# RCShield-arm-v0.net
KiCad netlist of a schematic drawn in EAGLE
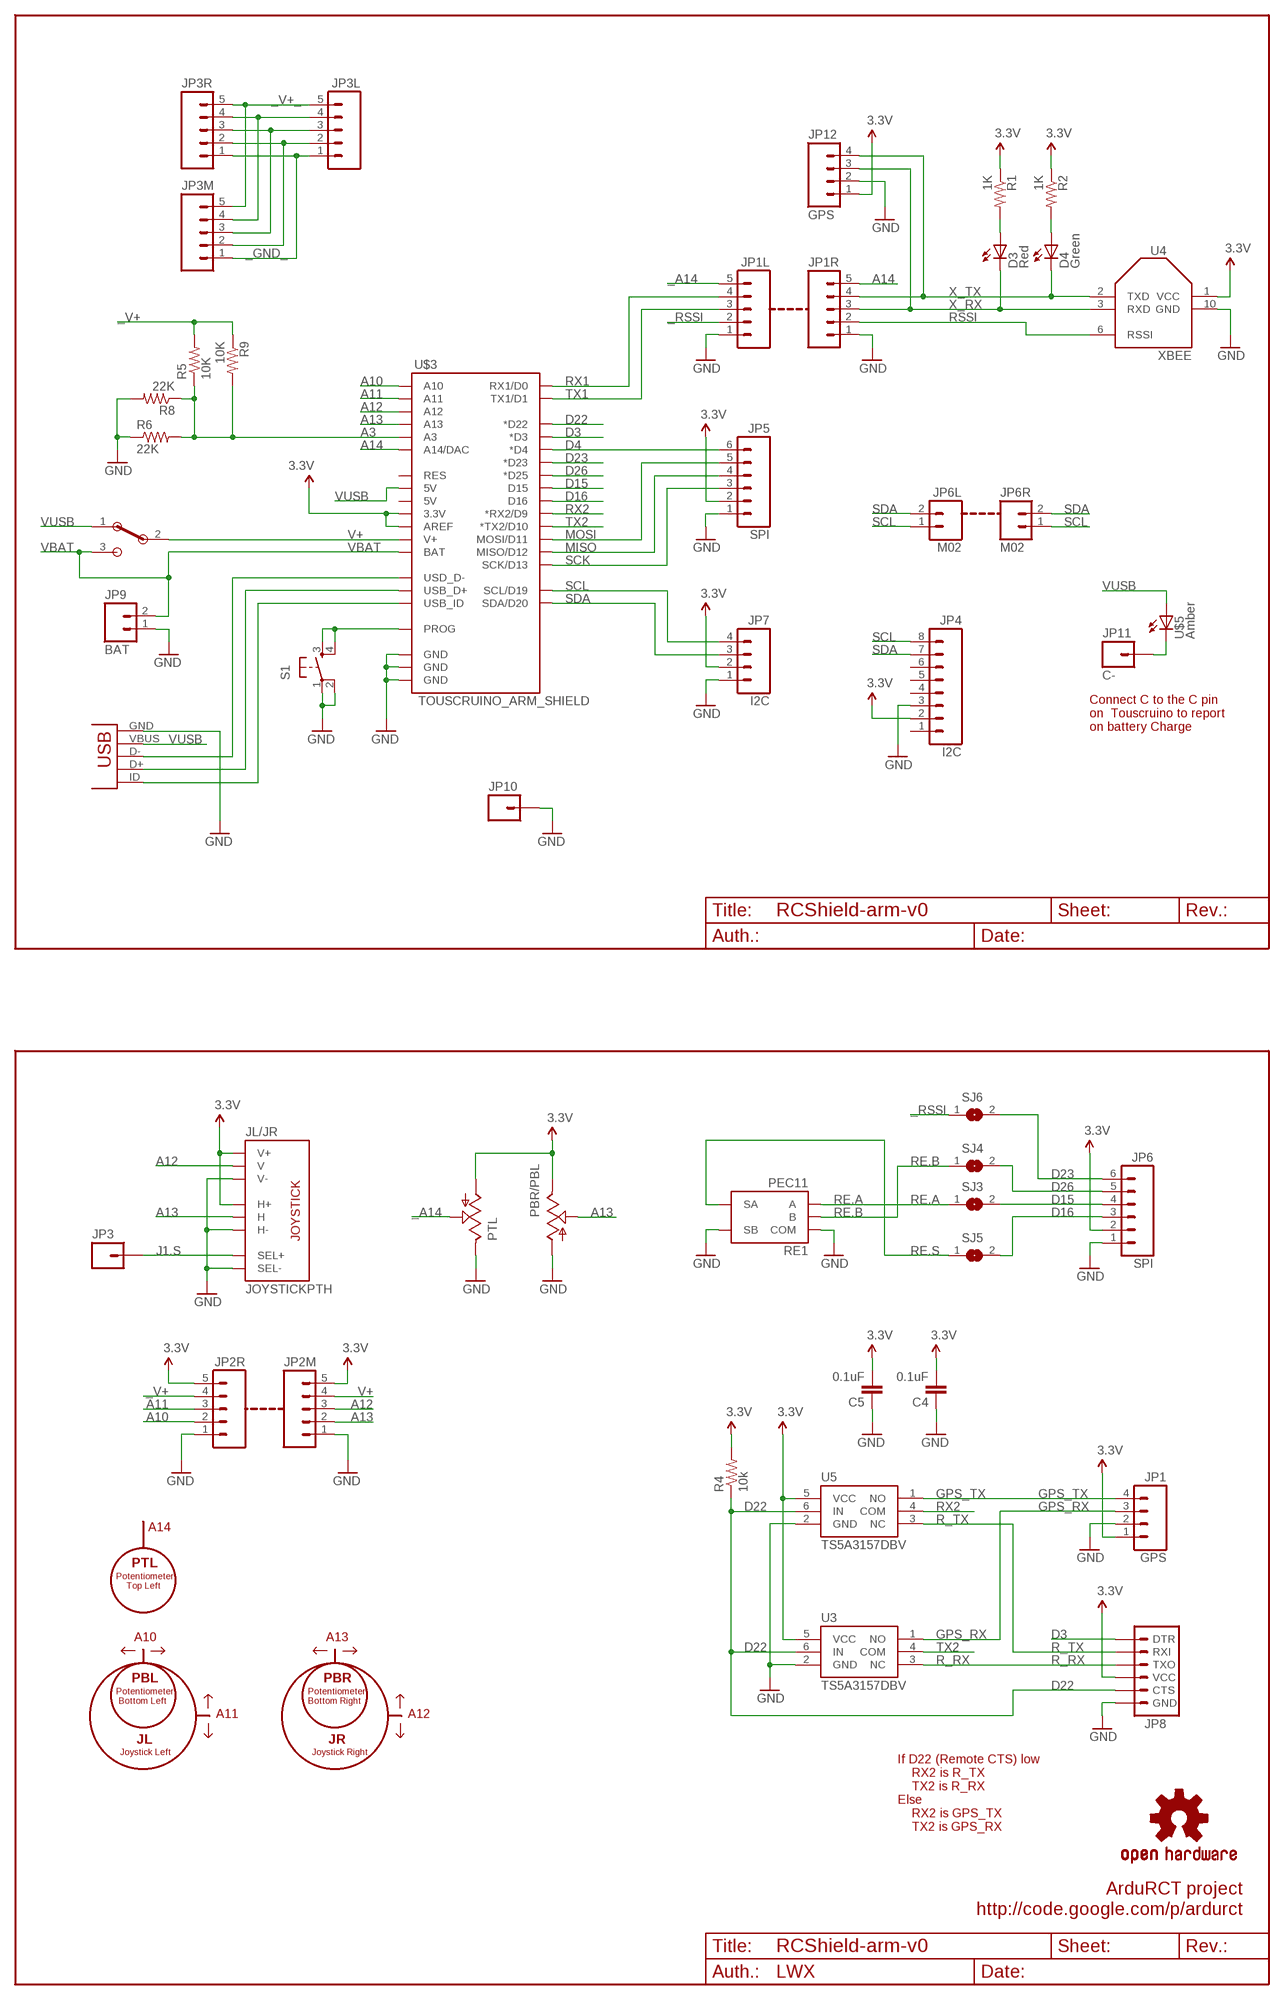
[diagram p0: schematic, sheet 1]

(export (version "E")
  (design (tool "Eeschema 10.0.6"))
  (components
    (comp (ref "C4")
      (value "0.1uF")
      (footprint "eagle-import:0805")
      (libsource (lib "eagle-import") (part "CAP0805"))
    )
    (comp (ref "C5")
      (value "0.1uF")
      (footprint "eagle-import:0805")
      (libsource (lib "eagle-import") (part "CAP0805"))
    )
    (comp (ref "D3")
      (value "Red")
      (footprint "eagle-import:LED")
      (libsource (lib "eagle-import") (part "LED"))
    )
    (comp (ref "D4")
      (value "Green")
      (footprint "eagle-import:LED")
      (libsource (lib "eagle-import") (part "LED"))
    )
    (comp (ref "JL/JR")
      (value "JOYSTICKPTH")
      (footprint "eagle-import:JOYSTICK")
      (libsource (lib "eagle-import") (part "JOYSTICKPTH"))
    )
    (comp (ref "JP1")
      (value "GPS")
      (footprint "eagle-import:1X04")
      (libsource (lib "eagle-import") (part "M04"))
    )
    (comp (ref "JP1L")
      (value "M05")
      (footprint "eagle-import:2+3")
      (libsource (lib "eagle-import") (part "M05"))
    )
    (comp (ref "JP1R")
      (value "M05")
      (footprint "eagle-import:2+3")
      (libsource (lib "eagle-import") (part "M05"))
    )
    (comp (ref "JP2M")
      (value "M05")
      (footprint "eagle-import:2+3")
      (libsource (lib "eagle-import") (part "M05"))
    )
    (comp (ref "JP2R")
      (value "M05")
      (footprint "eagle-import:2+3")
      (libsource (lib "eagle-import") (part "M05"))
    )
    (comp (ref "JP3")
      (value "M01PTH")
      (footprint "eagle-import:1X01")
      (libsource (lib "eagle-import") (part "M01PTH"))
    )
    (comp (ref "JP3L")
      (value "M05")
      (footprint "eagle-import:2+3")
      (libsource (lib "eagle-import") (part "M05"))
    )
    (comp (ref "JP3M")
      (value "M05")
      (footprint "eagle-import:2+3")
      (libsource (lib "eagle-import") (part "M05"))
    )
    (comp (ref "JP3R")
      (value "M05")
      (footprint "eagle-import:2+3")
      (libsource (lib "eagle-import") (part "M05"))
    )
    (comp (ref "JP4")
      (value "I2C")
      (footprint "eagle-import:1X08")
      (libsource (lib "eagle-import") (part "M08"))
    )
    (comp (ref "JP5")
      (value "SPI")
      (footprint "eagle-import:1X06")
      (libsource (lib "eagle-import") (part "M06SIP"))
    )
    (comp (ref "JP6")
      (value "SPI")
      (footprint "eagle-import:1X06")
      (libsource (lib "eagle-import") (part "M06SIP"))
    )
    (comp (ref "JP6L")
      (value "M02")
      (footprint "eagle-import:1X02")
      (libsource (lib "eagle-import") (part "M02"))
    )
    (comp (ref "JP6R")
      (value "M02")
      (footprint "eagle-import:1X02")
      (libsource (lib "eagle-import") (part "M02"))
    )
    (comp (ref "JP7")
      (value "I2C")
      (footprint "eagle-import:1X04")
      (libsource (lib "eagle-import") (part "M04"))
    )
    (comp (ref "JP8")
      (value "ARDUINO_SERIAL_PROGRAM")
      (footprint "eagle-import:1X06_F")
      (libsource (lib "eagle-import") (part "ARDUINO_SERIAL_PROGRAM"))
    )
    (comp (ref "JP9")
      (value "BAT")
      (footprint "eagle-import:1X02")
      (libsource (lib "eagle-import") (part "M02"))
    )
    (comp (ref "JP10")
      (value "M01PTH")
      (footprint "eagle-import:1X01")
      (libsource (lib "eagle-import") (part "M01PTH"))
    )
    (comp (ref "JP11")
      (value "C-")
      (footprint "eagle-import:1X01")
      (libsource (lib "eagle-import") (part "M01PTH"))
    )
    (comp (ref "JP12")
      (value "GPS")
      (footprint "eagle-import:1X04")
      (libsource (lib "eagle-import") (part "M04"))
    )
    (comp (ref "PBR/PBL")
      (value "POT")
      (footprint "eagle-import:ALPS_POT")
      (libsource (lib "eagle-import") (part "POT"))
    )
    (comp (ref "PTL")
      (value "POT")
      (footprint "eagle-import:ALPS_POT")
      (libsource (lib "eagle-import") (part "POT"))
    )
    (comp (ref "R1")
      (value "1K")
      (footprint "eagle-import:0805")
      (libsource (lib "eagle-import") (part "RESISTOR0805-RES"))
    )
    (comp (ref "R2")
      (value "1K")
      (footprint "eagle-import:0805")
      (libsource (lib "eagle-import") (part "RESISTOR0805-RES"))
    )
    (comp (ref "R4")
      (value "10k")
      (footprint "eagle-import:0805")
      (libsource (lib "eagle-import") (part "RESISTOR0805-RES"))
    )
    (comp (ref "R5")
      (value "10K")
      (footprint "eagle-import:0805")
      (libsource (lib "eagle-import") (part "RESISTOR0805-RES"))
    )
    (comp (ref "R6")
      (value "22K")
      (footprint "eagle-import:0805")
      (libsource (lib "eagle-import") (part "RESISTOR0805-RES"))
    )
    (comp (ref "R8")
      (value "22K")
      (footprint "eagle-import:0207_7")
      (libsource (lib "eagle-import") (part "R-US_0207/7"))
    )
    (comp (ref "R9")
      (value "10K")
      (footprint "eagle-import:0207_7")
      (libsource (lib "eagle-import") (part "R-US_0207/7"))
    )
    (comp (ref "RE1")
      (value "PEC11")
      (footprint "eagle-import:PEC11")
      (libsource (lib "eagle-import") (part "PEC11"))
    )
    (comp (ref "S1")
      (value "TAC_SWITCHPTH")
      (footprint "eagle-import:TACTILE-PTH")
      (libsource (lib "eagle-import") (part "TAC_SWITCHPTH"))
    )
    (comp (ref "S4")
      (value "EG1224")
      (footprint "eagle-import:EG1224")
      (libsource (lib "eagle-import") (part "EG1224"))
    )
    (comp (ref "SJ3") (value "SJ") (footprint "eagle-import:SJ") (libsource (lib "eagle-import") (part "SJ")))
    (comp (ref "SJ4") (value "SJ") (footprint "eagle-import:SJ") (libsource (lib "eagle-import") (part "SJ")))
    (comp (ref "SJ5") (value "SJ") (footprint "eagle-import:SJ") (libsource (lib "eagle-import") (part "SJ")))
    (comp (ref "SJ6") (value "SJ") (footprint "eagle-import:SJ") (libsource (lib "eagle-import") (part "SJ")))
    (comp (ref "U$1")
      (value "OSHW-LOGOM")
      (footprint "eagle-import:OSHW-LOGO-M")
      (libsource (lib "eagle-import") (part "OSHW-LOGOM"))
    )
    (comp (ref "U$3")
      (value "TOUSCRUINO_ARM_SHIELD")
      (footprint "eagle-import:TOUSCRUINO_ARM_SHIELD_SPLIT")
      (libsource (lib "eagle-import") (part "TOUSCRUINO_ARM_SHIELD"))
    )
    (comp (ref "U$5")
      (value "Amber")
      (footprint "eagle-import:LED")
      (libsource (lib "eagle-import") (part "LED"))
    )
    (comp (ref "U3")
      (value "TS5A3157DBV")
      (footprint "eagle-import:SOT23-6")
      (libsource (lib "eagle-import") (part "TS5A3157DBV"))
    )
    (comp (ref "U4")
      (value "XBEE")
      (footprint "eagle-import:XBEE-SMD")
      (libsource (lib "eagle-import") (part "XBEE-RSSI"))
    )
    (comp (ref "U5")
      (value "TS5A3157DBV")
      (footprint "eagle-import:SOT23-6")
      (libsource (lib "eagle-import") (part "TS5A3157DBV"))
    )
    (comp (ref "X1")
      (value "USB")
      (footprint "eagle-import:USB-MICROB")
      (libsource (lib "eagle-import") (part "USB"))
    )
  )
  (nets
    (net (code "1") (name "/A3") (class "Default")
      (node (ref "R5") (pin "1") (pinfunction "1_1") (pintype "passive"))
      (node (ref "R6") (pin "2") (pinfunction "2_2") (pintype "passive"))
      (node (ref "R8") (pin "1") (pinfunction "1_1") (pintype "passive"))
      (node (ref "R9") (pin "2") (pinfunction "2_2") (pintype "passive"))
      (node (ref "U$3") (pin "A3") (pinfunction "A3_A3") (pintype "bidirectional"))
    )
    (net (code "2") (name "/A10") (class "Default")
      (node (ref "JP2R") (pin "2") (pinfunction "2_2") (pintype "passive"))
      (node (ref "U$3") (pin "A10") (pinfunction "A10_A10") (pintype "bidirectional"))
    )
    (net (code "3") (name "/A11") (class "Default")
      (node (ref "JP2R") (pin "3") (pinfunction "3_3") (pintype "passive"))
      (node (ref "U$3") (pin "A11") (pinfunction "A11_A11") (pintype "bidirectional"))
    )
    (net (code "4") (name "/A12") (class "Default")
      (node (ref "JL/JR") (pin "V2") (pinfunction "V_V2") (pintype "bidirectional"))
      (node (ref "JP2M") (pin "3") (pinfunction "3_3") (pintype "passive"))
      (node (ref "U$3") (pin "A12") (pinfunction "A12_A12") (pintype "bidirectional"))
    )
    (net (code "5") (name "/A13") (class "Default")
      (node (ref "JL/JR") (pin "H2") (pinfunction "H_H2") (pintype "bidirectional"))
      (node (ref "JP2M") (pin "2") (pinfunction "2_2") (pintype "passive"))
      (node (ref "PBR/PBL") (pin "P$2") (pinfunction "S_P$2") (pintype "passive"))
      (node (ref "U$3") (pin "A13") (pinfunction "A13_A13") (pintype "bidirectional"))
    )
    (net (code "6") (name "/A14") (class "Default")
      (node (ref "JP1R") (pin "5") (pinfunction "5_5") (pintype "passive"))
      (node (ref "U$3") (pin "A14") (pinfunction "A14/DAC_A14") (pintype "bidirectional"))
    )
    (net (code "7") (name "/D3") (class "Default")
      (node (ref "JP8") (pin "1") (pinfunction "DTR_1") (pintype "passive"))
      (node (ref "U$3") (pin "D3") (pinfunction "*D3_D3") (pintype "bidirectional"))
    )
    (net (code "8") (name "/D4") (class "Default")
      (node (ref "JP5") (pin "6") (pinfunction "6_6") (pintype "passive"))
      (node (ref "U$3") (pin "D4") (pinfunction "*D4_D4") (pintype "bidirectional"))
    )
    (net (code "9") (name "/D15") (class "Default")
      (node (ref "JP6") (pin "4") (pinfunction "4_4") (pintype "passive"))
      (node (ref "SJ3") (pin "2") (pinfunction "2_2") (pintype "passive"))
      (node (ref "U$3") (pin "D15") (pinfunction "D15_D15") (pintype "bidirectional"))
    )
    (net (code "10") (name "/D16") (class "Default")
      (node (ref "JP6") (pin "3") (pinfunction "3_3") (pintype "passive"))
      (node (ref "SJ5") (pin "2") (pinfunction "2_2") (pintype "passive"))
      (node (ref "U$3") (pin "D16") (pinfunction "D16_D16") (pintype "bidirectional"))
    )
    (net (code "11") (name "/D22") (class "Default")
      (node (ref "JP8") (pin "5") (pinfunction "CTS_5") (pintype "passive"))
      (node (ref "R4") (pin "1") (pinfunction "1_1") (pintype "passive"))
      (node (ref "U$3") (pin "D22") (pinfunction "*D22_D22") (pintype "bidirectional"))
      (node (ref "U3") (pin "6") (pinfunction "IN_6") (pintype "bidirectional"))
      (node (ref "U5") (pin "6") (pinfunction "IN_6") (pintype "bidirectional"))
    )
    (net (code "12") (name "/D23") (class "Default")
      (node (ref "JP6") (pin "6") (pinfunction "6_6") (pintype "passive"))
      (node (ref "SJ6") (pin "2") (pinfunction "2_2") (pintype "passive"))
      (node (ref "U$3") (pin "D23") (pinfunction "*D23_D23") (pintype "bidirectional"))
    )
    (net (code "13") (name "/D26") (class "Default")
      (node (ref "JP6") (pin "5") (pinfunction "5_5") (pintype "passive"))
      (node (ref "SJ4") (pin "2") (pinfunction "2_2") (pintype "passive"))
      (node (ref "U$3") (pin "D25") (pinfunction "*D25_D25") (pintype "bidirectional"))
    )
    (net (code "14") (name "/GPS_RX") (class "Default")
      (node (ref "JP1") (pin "3") (pinfunction "3_3") (pintype "passive"))
      (node (ref "U3") (pin "1") (pinfunction "NO_1") (pintype "bidirectional"))
    )
    (net (code "15") (name "/GPS_TX") (class "Default")
      (node (ref "JP1") (pin "4") (pinfunction "4_4") (pintype "passive"))
      (node (ref "U5") (pin "1") (pinfunction "NO_1") (pintype "bidirectional"))
    )
    (net (code "16") (name "/J1.S") (class "Default")
      (node (ref "JL/JR") (pin "B1A") (pinfunction "SEL+_B1A") (pintype "bidirectional"))
      (node (ref "JP3") (pin "1") (pinfunction "1_1") (pintype "passive"))
    )
    (net (code "17") (name "/MISO") (class "Default")
      (node (ref "JP5") (pin "4") (pinfunction "4_4") (pintype "passive"))
      (node (ref "U$3") (pin "D12") (pinfunction "MISO/D12_D12") (pintype "bidirectional"))
    )
    (net (code "18") (name "/MOSI") (class "Default")
      (node (ref "JP5") (pin "5") (pinfunction "5_5") (pintype "passive"))
      (node (ref "U$3") (pin "D11") (pinfunction "MOSI/D11_D11") (pintype "bidirectional"))
    )
    (net (code "19") (name "/RE.A") (class "Default")
      (node (ref "RE1") (pin "A") (pinfunction "A_A") (pintype "bidirectional"))
      (node (ref "SJ3") (pin "1") (pinfunction "1_1") (pintype "passive"))
    )
    (net (code "20") (name "/RE.B") (class "Default")
      (node (ref "RE1") (pin "B") (pinfunction "B_B") (pintype "bidirectional"))
      (node (ref "SJ4") (pin "1") (pinfunction "1_1") (pintype "passive"))
    )
    (net (code "21") (name "/RE.S") (class "Default")
      (node (ref "RE1") (pin "S1") (pinfunction "SA_S1") (pintype "bidirectional"))
      (node (ref "SJ5") (pin "1") (pinfunction "1_1") (pintype "passive"))
    )
    (net (code "22") (name "/RSSI") (class "Default")
      (node (ref "JP1R") (pin "2") (pinfunction "2_2") (pintype "passive"))
      (node (ref "U4") (pin "6") (pinfunction "RSSI_6") (pintype "bidirectional"))
    )
    (net (code "23") (name "/RX1") (class "Default")
      (node (ref "JP1L") (pin "4") (pinfunction "4_4") (pintype "passive"))
      (node (ref "U$3") (pin "RX1/D0") (pinfunction "RX1/D0_RX1/D0") (pintype "bidirectional"))
    )
    (net (code "24") (name "/RX2") (class "Default")
      (node (ref "U$3") (pin "D9") (pinfunction "*RX2/D9_D9") (pintype "bidirectional"))
      (node (ref "U5") (pin "4") (pinfunction "COM_4") (pintype "bidirectional"))
    )
    (net (code "25") (name "/R_RX") (class "Default")
      (node (ref "JP8") (pin "3") (pinfunction "TXO_3") (pintype "passive"))
      (node (ref "U3") (pin "3") (pinfunction "NC_3") (pintype "bidirectional"))
    )
    (net (code "26") (name "/R_TX") (class "Default")
      (node (ref "JP8") (pin "2") (pinfunction "RXI_2") (pintype "passive"))
      (node (ref "U5") (pin "3") (pinfunction "NC_3") (pintype "bidirectional"))
    )
    (net (code "27") (name "/SCK") (class "Default")
      (node (ref "JP5") (pin "3") (pinfunction "3_3") (pintype "passive"))
      (node (ref "U$3") (pin "D13") (pinfunction "SCK/D13_D13") (pintype "bidirectional"))
    )
    (net (code "28") (name "/SCL") (class "Default")
      (node (ref "JP4") (pin "8") (pinfunction "8_8") (pintype "passive"))
      (node (ref "JP6L") (pin "1") (pinfunction "1_1") (pintype "passive"))
      (node (ref "JP6R") (pin "1") (pinfunction "1_1") (pintype "passive"))
      (node (ref "JP7") (pin "4") (pinfunction "4_4") (pintype "passive"))
      (node (ref "U$3") (pin "SCL") (pinfunction "SCL/D19_SCL") (pintype "bidirectional"))
    )
    (net (code "29") (name "/SDA") (class "Default")
      (node (ref "JP4") (pin "7") (pinfunction "7_7") (pintype "passive"))
      (node (ref "JP6L") (pin "2") (pinfunction "2_2") (pintype "passive"))
      (node (ref "JP6R") (pin "2") (pinfunction "2_2") (pintype "passive"))
      (node (ref "JP7") (pin "3") (pinfunction "3_3") (pintype "passive"))
      (node (ref "U$3") (pin "SDA") (pinfunction "SDA/D20_SDA") (pintype "bidirectional"))
    )
    (net (code "30") (name "/TX1") (class "Default")
      (node (ref "JP1L") (pin "3") (pinfunction "3_3") (pintype "passive"))
      (node (ref "U$3") (pin "TX1/D1") (pinfunction "TX1/D1_TX1/D1") (pintype "bidirectional"))
    )
    (net (code "31") (name "/TX2") (class "Default")
      (node (ref "U$3") (pin "D10") (pinfunction "*TX2/D10_D10") (pintype "bidirectional"))
      (node (ref "U3") (pin "4") (pinfunction "COM_4") (pintype "bidirectional"))
    )
    (net (code "32") (name "/V+") (class "Default")
      (node (ref "JP2M") (pin "4") (pinfunction "4_4") (pintype "passive"))
      (node (ref "S4") (pin "2") (pinfunction "2_2") (pintype "bidirectional"))
      (node (ref "U$3") (pin "V+") (pinfunction "V+_V+") (pintype "bidirectional"))
    )
    (net (code "33") (name "/VBAT") (class "Default")
      (node (ref "JP9") (pin "2") (pinfunction "2_2") (pintype "passive"))
      (node (ref "S4") (pin "3") (pinfunction "3_3") (pintype "bidirectional"))
      (node (ref "U$3") (pin "BAT") (pinfunction "BAT_BAT") (pintype "bidirectional"))
    )
    (net (code "34") (name "/VUSB") (class "Default")
      (node (ref "S4") (pin "1") (pinfunction "1_1") (pintype "bidirectional"))
      (node (ref "U$3") (pin "5V@1") (pinfunction "5V_5V@1") (pintype "bidirectional"))
      (node (ref "U$5") (pin "A1") (pinfunction "A_A1") (pintype "passive"))
      (node (ref "X1") (pin "VBUS") (pinfunction "VBUS_VBUS") (pintype "bidirectional"))
    )
    (net (code "35") (name "/X_RX") (class "Default")
      (node (ref "D3") (pin "C1") (pinfunction "C_C1") (pintype "passive"))
      (node (ref "JP12") (pin "3") (pinfunction "3_3") (pintype "passive"))
      (node (ref "JP1R") (pin "3") (pinfunction "3_3") (pintype "passive"))
      (node (ref "U4") (pin "3") (pinfunction "RXD_3") (pintype "bidirectional"))
    )
    (net (code "36") (name "/X_TX") (class "Default")
      (node (ref "D4") (pin "C1") (pinfunction "C_C1") (pintype "passive"))
      (node (ref "JP12") (pin "4") (pinfunction "4_4") (pintype "passive"))
      (node (ref "JP1R") (pin "4") (pinfunction "4_4") (pintype "passive"))
      (node (ref "U4") (pin "2") (pinfunction "TXD_2") (pintype "bidirectional"))
    )
    (net (code "37") (name "/_A14") (class "Default")
      (node (ref "JP1L") (pin "5") (pinfunction "5_5") (pintype "passive"))
      (node (ref "PTL") (pin "P$2") (pinfunction "S_P$2") (pintype "passive"))
    )
    (net (code "38") (name "/_GND_") (class "Default")
      (node (ref "JP3L") (pin "1") (pinfunction "1_1") (pintype "passive"))
      (node (ref "JP3M") (pin "1") (pinfunction "1_1") (pintype "passive"))
      (node (ref "JP3R") (pin "1") (pinfunction "1_1") (pintype "passive"))
    )
    (net (code "39") (name "/_RSSI") (class "Default")
      (node (ref "JP1L") (pin "2") (pinfunction "2_2") (pintype "passive"))
      (node (ref "SJ6") (pin "1") (pinfunction "1_1") (pintype "passive"))
    )
    (net (code "40") (name "/_V+") (class "Default")
      (node (ref "JP2R") (pin "4") (pinfunction "4_4") (pintype "passive"))
      (node (ref "R5") (pin "2") (pinfunction "2_2") (pintype "passive"))
      (node (ref "R9") (pin "1") (pinfunction "1_1") (pintype "passive"))
    )
    (net (code "41") (name "/_V+_") (class "Default")
      (node (ref "JP3L") (pin "5") (pinfunction "5_5") (pintype "passive"))
      (node (ref "JP3M") (pin "5") (pinfunction "5_5") (pintype "passive"))
      (node (ref "JP3R") (pin "5") (pinfunction "5_5") (pintype "passive"))
    )
    (net (code "42") (name "3.3V") (class "Default")
      (node (ref "C4") (pin "2") (pinfunction "2_2") (pintype "passive"))
      (node (ref "C5") (pin "2") (pinfunction "2_2") (pintype "passive"))
      (node (ref "JL/JR") (pin "H1") (pinfunction "H+_H1") (pintype "bidirectional"))
      (node (ref "JL/JR") (pin "V1") (pinfunction "V+_V1") (pintype "bidirectional"))
      (node (ref "JP1") (pin "1") (pinfunction "1_1") (pintype "passive"))
      (node (ref "JP12") (pin "1") (pinfunction "1_1") (pintype "passive"))
      (node (ref "JP2M") (pin "5") (pinfunction "5_5") (pintype "passive"))
      (node (ref "JP2R") (pin "5") (pinfunction "5_5") (pintype "passive"))
      (node (ref "JP4") (pin "2") (pinfunction "2_2") (pintype "passive"))
      (node (ref "JP5") (pin "2") (pinfunction "2_2") (pintype "passive"))
      (node (ref "JP6") (pin "2") (pinfunction "2_2") (pintype "passive"))
      (node (ref "JP7") (pin "2") (pinfunction "2_2") (pintype "passive"))
      (node (ref "JP8") (pin "4") (pinfunction "VCC_4") (pintype "passive"))
      (node (ref "PBR/PBL") (pin "P$1") (pinfunction "E_P$1") (pintype "passive"))
      (node (ref "PTL") (pin "P$3") (pinfunction "A_P$3") (pintype "passive"))
      (node (ref "R1") (pin "1") (pinfunction "1_1") (pintype "passive"))
      (node (ref "R2") (pin "1") (pinfunction "1_1") (pintype "passive"))
      (node (ref "R4") (pin "2") (pinfunction "2_2") (pintype "passive"))
      (node (ref "U$3") (pin "3.3V") (pinfunction "3.3V_3.3V") (pintype "bidirectional"))
      (node (ref "U$3") (pin "AREF") (pinfunction "AREF_AREF") (pintype "bidirectional"))
      (node (ref "U3") (pin "5") (pinfunction "VCC_5") (pintype "bidirectional"))
      (node (ref "U4") (pin "1") (pinfunction "VCC_1") (pintype "bidirectional"))
      (node (ref "U5") (pin "5") (pinfunction "VCC_5") (pintype "bidirectional"))
    )
    (net (code "43") (name "GND") (class "Default")
      (node (ref "C4") (pin "1") (pinfunction "1_1") (pintype "passive"))
      (node (ref "C5") (pin "1") (pinfunction "1_1") (pintype "passive"))
      (node (ref "JL/JR") (pin "B2A") (pinfunction "SEL-_B2A") (pintype "bidirectional"))
      (node (ref "JL/JR") (pin "H3") (pinfunction "H-_H3") (pintype "bidirectional"))
      (node (ref "JL/JR") (pin "V3") (pinfunction "V-_V3") (pintype "bidirectional"))
      (node (ref "JP1") (pin "2") (pinfunction "2_2") (pintype "passive"))
      (node (ref "JP10") (pin "1") (pinfunction "1_1") (pintype "passive"))
      (node (ref "JP12") (pin "2") (pinfunction "2_2") (pintype "passive"))
      (node (ref "JP1L") (pin "1") (pinfunction "1_1") (pintype "passive"))
      (node (ref "JP1R") (pin "1") (pinfunction "1_1") (pintype "passive"))
      (node (ref "JP2M") (pin "1") (pinfunction "1_1") (pintype "passive"))
      (node (ref "JP2R") (pin "1") (pinfunction "1_1") (pintype "passive"))
      (node (ref "JP4") (pin "3") (pinfunction "3_3") (pintype "passive"))
      (node (ref "JP5") (pin "1") (pinfunction "1_1") (pintype "passive"))
      (node (ref "JP6") (pin "1") (pinfunction "1_1") (pintype "passive"))
      (node (ref "JP7") (pin "1") (pinfunction "1_1") (pintype "passive"))
      (node (ref "JP8") (pin "6") (pinfunction "GND_6") (pintype "passive"))
      (node (ref "JP9") (pin "1") (pinfunction "1_1") (pintype "passive"))
      (node (ref "PBR/PBL") (pin "P$3") (pinfunction "A_P$3") (pintype "passive"))
      (node (ref "PTL") (pin "P$1") (pinfunction "E_P$1") (pintype "passive"))
      (node (ref "R6") (pin "1") (pinfunction "1_1") (pintype "passive"))
      (node (ref "R8") (pin "2") (pinfunction "2_2") (pintype "passive"))
      (node (ref "RE1") (pin "C") (pinfunction "COM_C") (pintype "bidirectional"))
      (node (ref "RE1") (pin "S2") (pinfunction "SB_S2") (pintype "bidirectional"))
      (node (ref "S1") (pin "1") (pinfunction "1_1") (pintype "passive"))
      (node (ref "S1") (pin "2") (pinfunction "2_2") (pintype "passive"))
      (node (ref "U$3") (pin "GND@0") (pinfunction "GND_GND@0") (pintype "bidirectional"))
      (node (ref "U$3") (pin "GND@1") (pinfunction "GND_GND@1") (pintype "bidirectional"))
      (node (ref "U$3") (pin "GND@2") (pinfunction "GND_GND@2") (pintype "bidirectional"))
      (node (ref "U3") (pin "2") (pinfunction "GND_2") (pintype "bidirectional"))
      (node (ref "U4") (pin "10") (pinfunction "GND_10") (pintype "bidirectional"))
      (node (ref "U5") (pin "2") (pinfunction "GND_2") (pintype "bidirectional"))
      (node (ref "X1") (pin "GND") (pinfunction "GND_GND") (pintype "bidirectional"))
    )
    (net (code "44") (name "Net-(D3-A)") (class "Default")
      (node (ref "D3") (pin "A1") (pinfunction "A_A1") (pintype "passive"))
      (node (ref "R1") (pin "2") (pinfunction "2_2") (pintype "passive"))
    )
    (net (code "45") (name "Net-(D4-A)") (class "Default")
      (node (ref "D4") (pin "A1") (pinfunction "A_A1") (pintype "passive"))
      (node (ref "R2") (pin "2") (pinfunction "2_2") (pintype "passive"))
    )
    (net (code "46") (name "Net-(JP3L-Pad2)") (class "Default")
      (node (ref "JP3L") (pin "2") (pinfunction "2_2") (pintype "passive"))
      (node (ref "JP3M") (pin "2") (pinfunction "2_2") (pintype "passive"))
      (node (ref "JP3R") (pin "2") (pinfunction "2_2") (pintype "passive"))
    )
    (net (code "47") (name "Net-(JP3L-Pad3)") (class "Default")
      (node (ref "JP3L") (pin "3") (pinfunction "3_3") (pintype "passive"))
      (node (ref "JP3M") (pin "3") (pinfunction "3_3") (pintype "passive"))
      (node (ref "JP3R") (pin "3") (pinfunction "3_3") (pintype "passive"))
    )
    (net (code "48") (name "Net-(JP3L-Pad4)") (class "Default")
      (node (ref "JP3L") (pin "4") (pinfunction "4_4") (pintype "passive"))
      (node (ref "JP3M") (pin "4") (pinfunction "4_4") (pintype "passive"))
      (node (ref "JP3R") (pin "4") (pinfunction "4_4") (pintype "passive"))
    )
    (net (code "49") (name "Net-(S1-Pad3)") (class "Default")
      (node (ref "S1") (pin "3") (pinfunction "3_3") (pintype "passive"))
      (node (ref "S1") (pin "4") (pinfunction "4_4") (pintype "passive"))
      (node (ref "U$3") (pin "PROG") (pinfunction "PROG_PROG") (pintype "bidirectional"))
    )
    (net (code "50") (name "Net-(U$3-PadUSB_D+)") (class "Default")
      (node (ref "U$3") (pin "USB_D+") (pinfunction "USB_D+_USB_D+") (pintype "bidirectional"))
      (node (ref "X1") (pin "D+") (pinfunction "D+_D+") (pintype "bidirectional"))
    )
    (net (code "51") (name "Net-(U$3-PadUSB_ID)") (class "Default")
      (node (ref "U$3") (pin "USB_ID") (pinfunction "USB_ID_USB_ID") (pintype "bidirectional"))
      (node (ref "X1") (pin "ID") (pinfunction "ID_ID") (pintype "bidirectional"))
    )
    (net (code "52") (name "Net-(U$3-USD_D-)") (class "Default")
      (node (ref "U$3") (pin "USB_D-") (pinfunction "USD_D-_USB_D-") (pintype "bidirectional"))
      (node (ref "X1") (pin "D-") (pinfunction "D-_D-") (pintype "bidirectional"))
    )
    (net (code "53") (name "Net-(U$5-C)") (class "Default")
      (node (ref "JP11") (pin "1") (pinfunction "1_1") (pintype "passive"))
      (node (ref "U$5") (pin "C1") (pinfunction "C_C1") (pintype "passive"))
    )
    (net (code "54") (name "unconnected-(JP4-Pad1)") (class "Default")
      (node (ref "JP4") (pin "1") (pinfunction "1_1") (pintype "passive"))
    )
    (net (code "55") (name "unconnected-(JP4-Pad4)") (class "Default")
      (node (ref "JP4") (pin "4") (pinfunction "4_4") (pintype "passive"))
    )
    (net (code "56") (name "unconnected-(JP4-Pad5)") (class "Default")
      (node (ref "JP4") (pin "5") (pinfunction "5_5") (pintype "passive"))
    )
    (net (code "57") (name "unconnected-(JP4-Pad6)") (class "Default")
      (node (ref "JP4") (pin "6") (pinfunction "6_6") (pintype "passive"))
    )
    (net (code "58") (name "unconnected-(U$3-5V-Pad5V@0)") (class "Default")
      (node (ref "U$3") (pin "5V@0") (pinfunction "5V_5V@0") (pintype "bidirectional"))
    )
    (net (code "59") (name "unconnected-(U$3-PadRES)") (class "Default")
      (node (ref "U$3") (pin "RES") (pinfunction "RES_RES") (pintype "bidirectional"))
    )
  )
)
